# MultiCoupler.net
KiCad netlist of a schematic drawn in EAGLE
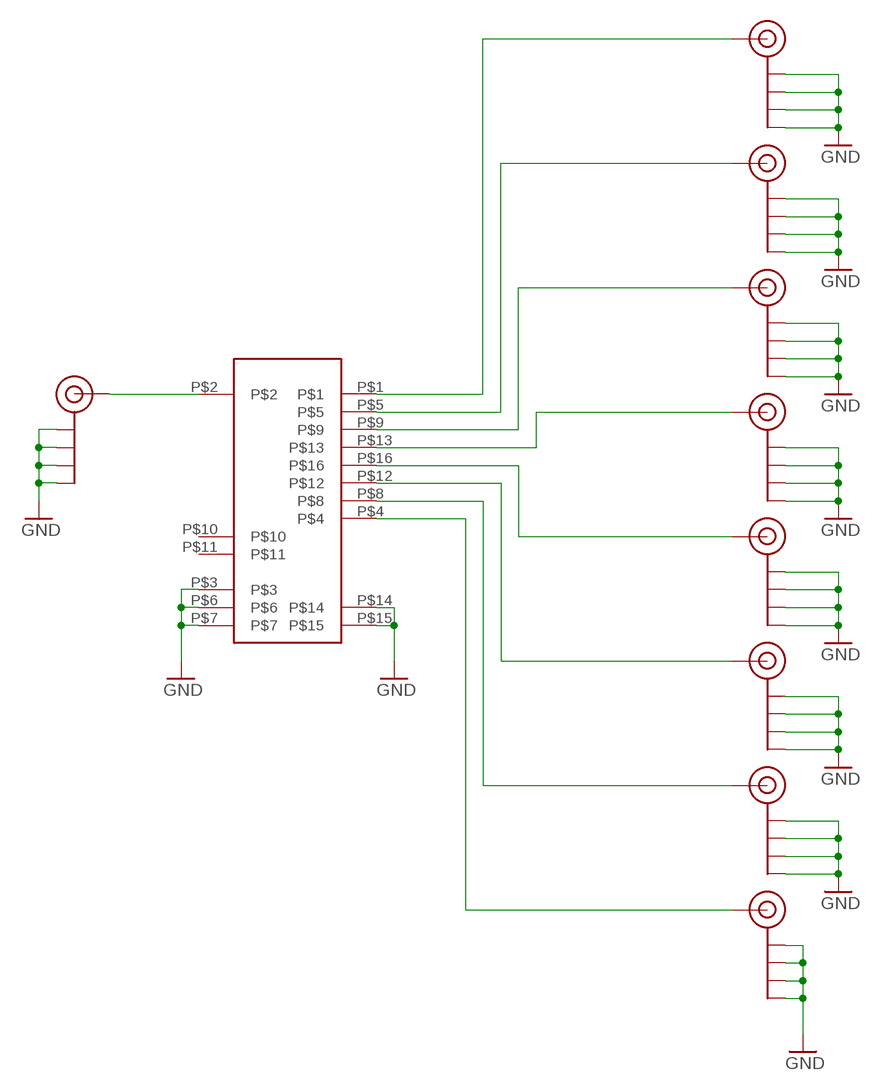
[diagram p0: schematic, sheet 1]

(export (version "E")
  (design (tool "Eeschema 10.0.6"))
  (components
    (comp (ref "J$1")
      (value "SMA_EDGE")
      (footprint "eagle-import:SMA-EDGE")
      (libsource (lib "eagle-import") (part "SMA_EDGE"))
    )
    (comp (ref "J$2")
      (value "SMA_EDGE")
      (footprint "eagle-import:SMA-EDGE")
      (libsource (lib "eagle-import") (part "SMA_EDGE"))
    )
    (comp (ref "J$3")
      (value "SMA_EDGE")
      (footprint "eagle-import:SMA-EDGE")
      (libsource (lib "eagle-import") (part "SMA_EDGE"))
    )
    (comp (ref "J$4")
      (value "SMA_EDGE")
      (footprint "eagle-import:SMA-EDGE")
      (libsource (lib "eagle-import") (part "SMA_EDGE"))
    )
    (comp (ref "J$5")
      (value "SMA_EDGE")
      (footprint "eagle-import:SMA-EDGE")
      (libsource (lib "eagle-import") (part "SMA_EDGE"))
    )
    (comp (ref "J$6")
      (value "SMA_EDGE")
      (footprint "eagle-import:SMA-EDGE")
      (libsource (lib "eagle-import") (part "SMA_EDGE"))
    )
    (comp (ref "J$7")
      (value "SMA_EDGE")
      (footprint "eagle-import:SMA-EDGE")
      (libsource (lib "eagle-import") (part "SMA_EDGE"))
    )
    (comp (ref "J$8")
      (value "SMA_EDGE")
      (footprint "eagle-import:SMA-EDGE")
      (libsource (lib "eagle-import") (part "SMA_EDGE"))
    )
    (comp (ref "J$9")
      (value "SMA_EDGE")
      (footprint "eagle-import:SMA-EDGE")
      (libsource (lib "eagle-import") (part "SMA_EDGE"))
    )
    (comp (ref "U$1")
      (value "PSC-8-1-75THROUGH_HOLE")
      (footprint "eagle-import:PSC-8-1-75")
      (libsource (lib "eagle-import") (part "PSC-8-1-75THROUGH_HOLE"))
    )
  )
  (nets
    (net (code "1") (name "GND") (class "Default")
      (node (ref "J$1") (pin "GND@0") (pinfunction "GND_GND@0") (pintype "bidirectional"))
      (node (ref "J$1") (pin "GND@1") (pinfunction "GND_GND@1") (pintype "bidirectional"))
      (node (ref "J$1") (pin "GND@2") (pinfunction "GND_GND@2") (pintype "bidirectional"))
      (node (ref "J$1") (pin "GND@3") (pinfunction "GND_GND@3") (pintype "bidirectional"))
      (node (ref "J$2") (pin "GND@0") (pinfunction "GND_GND@0") (pintype "bidirectional"))
      (node (ref "J$2") (pin "GND@1") (pinfunction "GND_GND@1") (pintype "bidirectional"))
      (node (ref "J$2") (pin "GND@2") (pinfunction "GND_GND@2") (pintype "bidirectional"))
      (node (ref "J$2") (pin "GND@3") (pinfunction "GND_GND@3") (pintype "bidirectional"))
      (node (ref "J$3") (pin "GND@0") (pinfunction "GND_GND@0") (pintype "bidirectional"))
      (node (ref "J$3") (pin "GND@1") (pinfunction "GND_GND@1") (pintype "bidirectional"))
      (node (ref "J$3") (pin "GND@2") (pinfunction "GND_GND@2") (pintype "bidirectional"))
      (node (ref "J$3") (pin "GND@3") (pinfunction "GND_GND@3") (pintype "bidirectional"))
      (node (ref "J$4") (pin "GND@0") (pinfunction "GND_GND@0") (pintype "bidirectional"))
      (node (ref "J$4") (pin "GND@1") (pinfunction "GND_GND@1") (pintype "bidirectional"))
      (node (ref "J$4") (pin "GND@2") (pinfunction "GND_GND@2") (pintype "bidirectional"))
      (node (ref "J$4") (pin "GND@3") (pinfunction "GND_GND@3") (pintype "bidirectional"))
      (node (ref "J$5") (pin "GND@0") (pinfunction "GND_GND@0") (pintype "bidirectional"))
      (node (ref "J$5") (pin "GND@1") (pinfunction "GND_GND@1") (pintype "bidirectional"))
      (node (ref "J$5") (pin "GND@2") (pinfunction "GND_GND@2") (pintype "bidirectional"))
      (node (ref "J$5") (pin "GND@3") (pinfunction "GND_GND@3") (pintype "bidirectional"))
      (node (ref "J$6") (pin "GND@0") (pinfunction "GND_GND@0") (pintype "bidirectional"))
      (node (ref "J$6") (pin "GND@1") (pinfunction "GND_GND@1") (pintype "bidirectional"))
      (node (ref "J$6") (pin "GND@2") (pinfunction "GND_GND@2") (pintype "bidirectional"))
      (node (ref "J$6") (pin "GND@3") (pinfunction "GND_GND@3") (pintype "bidirectional"))
      (node (ref "J$7") (pin "GND@0") (pinfunction "GND_GND@0") (pintype "bidirectional"))
      (node (ref "J$7") (pin "GND@1") (pinfunction "GND_GND@1") (pintype "bidirectional"))
      (node (ref "J$7") (pin "GND@2") (pinfunction "GND_GND@2") (pintype "bidirectional"))
      (node (ref "J$7") (pin "GND@3") (pinfunction "GND_GND@3") (pintype "bidirectional"))
      (node (ref "J$8") (pin "GND@0") (pinfunction "GND_GND@0") (pintype "bidirectional"))
      (node (ref "J$8") (pin "GND@1") (pinfunction "GND_GND@1") (pintype "bidirectional"))
      (node (ref "J$8") (pin "GND@2") (pinfunction "GND_GND@2") (pintype "bidirectional"))
      (node (ref "J$8") (pin "GND@3") (pinfunction "GND_GND@3") (pintype "bidirectional"))
      (node (ref "J$9") (pin "GND@0") (pinfunction "GND_GND@0") (pintype "bidirectional"))
      (node (ref "J$9") (pin "GND@1") (pinfunction "GND_GND@1") (pintype "bidirectional"))
      (node (ref "J$9") (pin "GND@2") (pinfunction "GND_GND@2") (pintype "bidirectional"))
      (node (ref "J$9") (pin "GND@3") (pinfunction "GND_GND@3") (pintype "bidirectional"))
      (node (ref "U$1") (pin "P$14") (pinfunction "P$14_P$14") (pintype "bidirectional"))
      (node (ref "U$1") (pin "P$15") (pinfunction "P$15_P$15") (pintype "bidirectional"))
      (node (ref "U$1") (pin "P$3") (pinfunction "P$3_P$3") (pintype "bidirectional"))
      (node (ref "U$1") (pin "P$6") (pinfunction "P$6_P$6") (pintype "bidirectional"))
      (node (ref "U$1") (pin "P$7") (pinfunction "P$7_P$7") (pintype "bidirectional"))
    )
    (net (code "2") (name "Net-(J$1-SIGNAL)") (class "Default")
      (node (ref "J$1") (pin "SIG") (pinfunction "SIGNAL_SIG") (pintype "bidirectional"))
      (node (ref "U$1") (pin "P$2") (pinfunction "P$2_P$2") (pintype "bidirectional"))
    )
    (net (code "3") (name "Net-(J$2-SIGNAL)") (class "Default")
      (node (ref "J$2") (pin "SIG") (pinfunction "SIGNAL_SIG") (pintype "bidirectional"))
      (node (ref "U$1") (pin "P$13") (pinfunction "P$13_P$13") (pintype "bidirectional"))
    )
    (net (code "4") (name "Net-(J$3-SIGNAL)") (class "Default")
      (node (ref "J$3") (pin "SIG") (pinfunction "SIGNAL_SIG") (pintype "bidirectional"))
      (node (ref "U$1") (pin "P$16") (pinfunction "P$16_P$16") (pintype "bidirectional"))
    )
    (net (code "5") (name "Net-(J$4-SIGNAL)") (class "Default")
      (node (ref "J$4") (pin "SIG") (pinfunction "SIGNAL_SIG") (pintype "bidirectional"))
      (node (ref "U$1") (pin "P$12") (pinfunction "P$12_P$12") (pintype "bidirectional"))
    )
    (net (code "6") (name "Net-(J$5-SIGNAL)") (class "Default")
      (node (ref "J$5") (pin "SIG") (pinfunction "SIGNAL_SIG") (pintype "bidirectional"))
      (node (ref "U$1") (pin "P$8") (pinfunction "P$8_P$8") (pintype "bidirectional"))
    )
    (net (code "7") (name "Net-(J$6-SIGNAL)") (class "Default")
      (node (ref "J$6") (pin "SIG") (pinfunction "SIGNAL_SIG") (pintype "bidirectional"))
      (node (ref "U$1") (pin "P$4") (pinfunction "P$4_P$4") (pintype "bidirectional"))
    )
    (net (code "8") (name "Net-(J$7-SIGNAL)") (class "Default")
      (node (ref "J$7") (pin "SIG") (pinfunction "SIGNAL_SIG") (pintype "bidirectional"))
      (node (ref "U$1") (pin "P$9") (pinfunction "P$9_P$9") (pintype "bidirectional"))
    )
    (net (code "9") (name "Net-(J$8-SIGNAL)") (class "Default")
      (node (ref "J$8") (pin "SIG") (pinfunction "SIGNAL_SIG") (pintype "bidirectional"))
      (node (ref "U$1") (pin "P$5") (pinfunction "P$5_P$5") (pintype "bidirectional"))
    )
    (net (code "10") (name "Net-(J$9-SIGNAL)") (class "Default")
      (node (ref "J$9") (pin "SIG") (pinfunction "SIGNAL_SIG") (pintype "bidirectional"))
      (node (ref "U$1") (pin "P$1") (pinfunction "P$1_P$1") (pintype "bidirectional"))
    )
    (net (code "11") (name "unconnected-(U$1-PadP$10)") (class "Default")
      (node (ref "U$1") (pin "P$10") (pinfunction "P$10_P$10") (pintype "bidirectional"))
    )
    (net (code "12") (name "unconnected-(U$1-PadP$11)") (class "Default")
      (node (ref "U$1") (pin "P$11") (pinfunction "P$11_P$11") (pintype "bidirectional"))
    )
  )
)
